# jar.net
KiCad netlist of a schematic drawn in EAGLE
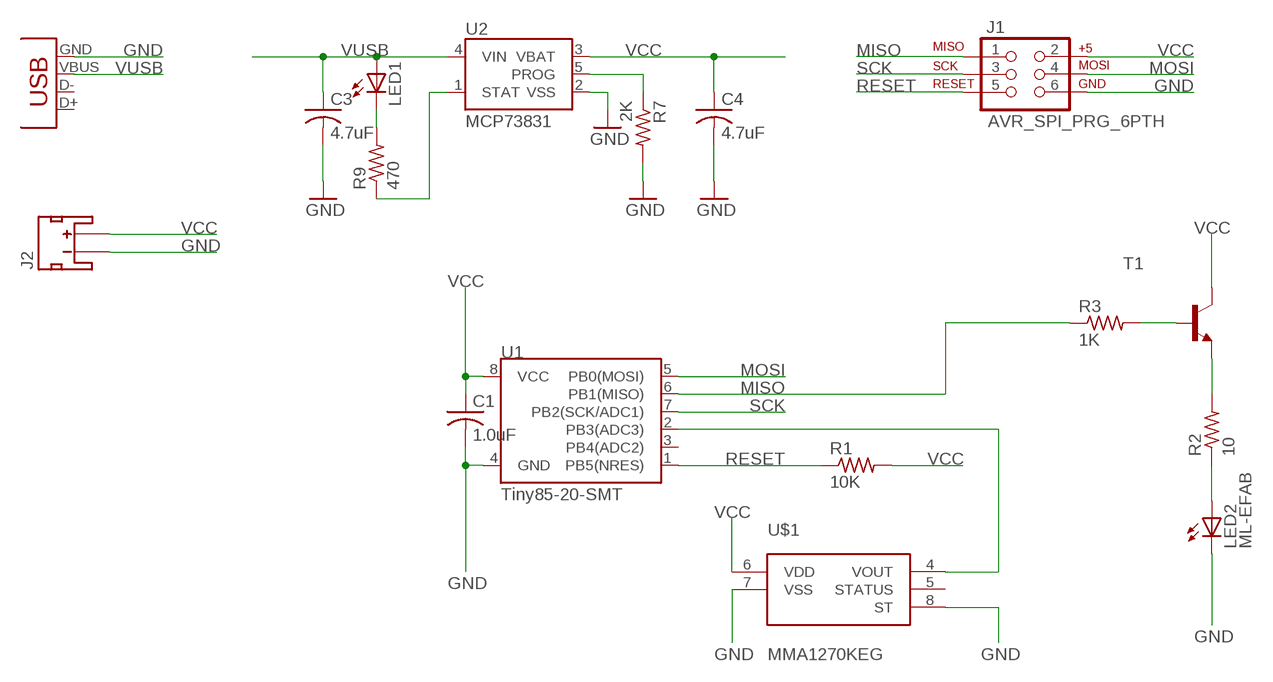
[diagram p0: schematic, sheet 1]

(export (version "E")
  (design (tool "Eeschema 10.0.6"))
  (components
    (comp (ref "C1")
      (value "1.0uF")
      (footprint "eagle-import:C1206")
      (libsource (lib "eagle-import") (part "C-USC1206"))
    )
    (comp (ref "C3")
      (value "4.7uF")
      (footprint "eagle-import:C1206")
      (libsource (lib "eagle-import") (part "C-USC1206"))
    )
    (comp (ref "C4")
      (value "4.7uF")
      (footprint "eagle-import:C1206")
      (libsource (lib "eagle-import") (part "C-USC1206"))
    )
    (comp (ref "J1")
      (value "AVR_SPI_PRG_6PTH")
      (footprint "eagle-import:2X3")
      (libsource (lib "eagle-import") (part "AVR_SPI_PRG_6PTH"))
    )
    (comp (ref "J2")
      (value "JST_2MM_MALE")
      (footprint "eagle-import:JST-2-SMD")
      (libsource (lib "eagle-import") (part "JST_2MM_MALE"))
    )
    (comp (ref "JP1")
      (value "USB-B-VERTICAL")
      (footprint "eagle-import:USB_MINIB_VERTICAL")
      (libsource (lib "eagle-import") (part "USB-B-VERTICAL"))
    )
    (comp (ref "LED1")
      (value "LEDSMT1206")
      (footprint "eagle-import:1206")
      (libsource (lib "eagle-import") (part "LEDSMT1206"))
    )
    (comp (ref "LED2")
      (value "ML-EFAB")
      (footprint "eagle-import:ML-E-FAB")
      (libsource (lib "eagle-import") (part "ML-EFAB"))
    )
    (comp (ref "R1")
      (value "10K")
      (footprint "eagle-import:R1206")
      (libsource (lib "eagle-import") (part "R-US_R1206"))
    )
    (comp (ref "R2")
      (value "10")
      (footprint "eagle-import:R1206")
      (libsource (lib "eagle-import") (part "R-US_R1206"))
    )
    (comp (ref "R3")
      (value "1K")
      (footprint "eagle-import:R1206")
      (libsource (lib "eagle-import") (part "R-US_R1206"))
    )
    (comp (ref "R7")
      (value "2K")
      (footprint "eagle-import:R1206")
      (libsource (lib "eagle-import") (part "R-US_R1206"))
    )
    (comp (ref "R9")
      (value "470")
      (footprint "eagle-import:R1206")
      (libsource (lib "eagle-import") (part "R-US_R1206"))
    )
    (comp (ref "T1")
      (value "MMBT3904LT1-NPN-SOT23-BEC")
      (footprint "eagle-import:SOT23-BEC")
      (libsource (lib "eagle-import") (part "-NPN-SOT23-BECMMBT3904LT1"))
    )
    (comp (ref "U$1")
      (value "MMA1270KEG")
      (footprint "eagle-import:SOIC16")
      (libsource (lib "eagle-import") (part "MMA1270KEG"))
    )
    (comp (ref "U1")
      (value "Tiny85-20-SMT")
      (footprint "eagle-import:SO08-EIAJ")
      (libsource (lib "eagle-import") (part "ATTINY45TINY85-20-SMT"))
    )
    (comp (ref "U2")
      (value "MCP73831")
      (footprint "eagle-import:SOT23-5")
      (libsource (lib "eagle-import") (part "MCP73831"))
    )
  )
  (nets
    (net (code "1") (name "/MISO") (class "Default")
      (node (ref "J1") (pin "1") (pinfunction "1_1") (pintype "passive"))
      (node (ref "R3") (pin "1") (pinfunction "1_1") (pintype "passive"))
      (node (ref "U1") (pin "6") (pinfunction "PB1(MISO)_6") (pintype "bidirectional"))
    )
    (net (code "2") (name "/MOSI") (class "Default")
      (node (ref "J1") (pin "4") (pinfunction "4_4") (pintype "passive"))
      (node (ref "U1") (pin "5") (pinfunction "PB0(MOSI)_5") (pintype "bidirectional"))
    )
    (net (code "3") (name "/RESET") (class "Default")
      (node (ref "J1") (pin "5") (pinfunction "5_5") (pintype "passive"))
      (node (ref "R1") (pin "1") (pinfunction "1_1") (pintype "passive"))
      (node (ref "U1") (pin "1") (pinfunction "PB5(NRES)_1") (pintype "bidirectional"))
    )
    (net (code "4") (name "/SCK") (class "Default")
      (node (ref "J1") (pin "3") (pinfunction "3_3") (pintype "passive"))
      (node (ref "U1") (pin "7") (pinfunction "PB2(SCK/ADC1)_7") (pintype "bidirectional"))
    )
    (net (code "5") (name "/VCC") (class "Default")
      (node (ref "C1") (pin "1") (pinfunction "1_1") (pintype "passive"))
      (node (ref "C4") (pin "1") (pinfunction "1_1") (pintype "passive"))
      (node (ref "J1") (pin "2") (pinfunction "2_2") (pintype "passive"))
      (node (ref "J2") (pin "2") (pinfunction "+_2") (pintype "bidirectional"))
      (node (ref "R1") (pin "2") (pinfunction "2_2") (pintype "passive"))
      (node (ref "T1") (pin "C") (pinfunction "C_C") (pintype "passive"))
      (node (ref "U$1") (pin "6") (pinfunction "VDD_6") (pintype "bidirectional"))
      (node (ref "U1") (pin "8") (pinfunction "VCC_8") (pintype "bidirectional"))
      (node (ref "U2") (pin "3") (pinfunction "VBAT_3") (pintype "power_in"))
    )
    (net (code "6") (name "/VUSB") (class "Default")
      (node (ref "C3") (pin "1") (pinfunction "1_1") (pintype "passive"))
      (node (ref "JP1") (pin "VBUS") (pinfunction "VBUS_VBUS") (pintype "bidirectional"))
      (node (ref "LED1") (pin "A") (pinfunction "A_A") (pintype "passive"))
      (node (ref "U2") (pin "4") (pinfunction "VIN_4") (pintype "power_in"))
    )
    (net (code "7") (name "GND") (class "Default")
      (node (ref "C1") (pin "2") (pinfunction "2_2") (pintype "passive"))
      (node (ref "C3") (pin "2") (pinfunction "2_2") (pintype "passive"))
      (node (ref "C4") (pin "2") (pinfunction "2_2") (pintype "passive"))
      (node (ref "J1") (pin "6") (pinfunction "6_6") (pintype "passive"))
      (node (ref "J2") (pin "1") (pinfunction "-_1") (pintype "bidirectional"))
      (node (ref "JP1") (pin "GND") (pinfunction "GND_GND") (pintype "bidirectional"))
      (node (ref "LED2") (pin "C@1") (pinfunction "C_C@1") (pintype "passive"))
      (node (ref "R7") (pin "2") (pinfunction "2_2") (pintype "passive"))
      (node (ref "U$1") (pin "7") (pinfunction "VSS_7") (pintype "bidirectional"))
      (node (ref "U$1") (pin "8") (pinfunction "ST_8") (pintype "bidirectional"))
      (node (ref "U1") (pin "4") (pinfunction "GND_4") (pintype "bidirectional"))
      (node (ref "U2") (pin "2") (pinfunction "VSS_2") (pintype "power_in"))
    )
    (net (code "8") (name "Net-(LED1-PadC)") (class "Default")
      (node (ref "LED1") (pin "C") (pinfunction "C_C") (pintype "passive"))
      (node (ref "R9") (pin "2") (pinfunction "2_2") (pintype "passive"))
    )
    (net (code "9") (name "Net-(LED2A-A-PadA@1)") (class "Default")
      (node (ref "LED2") (pin "A@1") (pinfunction "A_A@1") (pintype "passive"))
      (node (ref "R2") (pin "1") (pinfunction "1_1") (pintype "passive"))
    )
    (net (code "10") (name "Net-(R2-Pad2)") (class "Default")
      (node (ref "R2") (pin "2") (pinfunction "2_2") (pintype "passive"))
      (node (ref "T1") (pin "E") (pinfunction "E_E") (pintype "passive"))
    )
    (net (code "11") (name "Net-(R3-Pad2)") (class "Default")
      (node (ref "R3") (pin "2") (pinfunction "2_2") (pintype "passive"))
      (node (ref "T1") (pin "B") (pinfunction "B_B") (pintype "passive"))
    )
    (net (code "12") (name "Net-(U$1-VOUT)") (class "Default")
      (node (ref "U$1") (pin "4") (pinfunction "VOUT_4") (pintype "bidirectional"))
      (node (ref "U1") (pin "2") (pinfunction "PB3(ADC3)_2") (pintype "bidirectional"))
    )
    (net (code "13") (name "Net-(U2-PROG)") (class "Default")
      (node (ref "R7") (pin "1") (pinfunction "1_1") (pintype "passive"))
      (node (ref "U2") (pin "5") (pinfunction "PROG_5") (pintype "input"))
    )
    (net (code "14") (name "Net-(U2-STAT)") (class "Default")
      (node (ref "R9") (pin "1") (pinfunction "1_1") (pintype "passive"))
      (node (ref "U2") (pin "1") (pinfunction "STAT_1") (pintype "output"))
    )
    (net (code "15") (name "unconnected-(J2-PAD1-PadNC1)") (class "Default")
      (node (ref "J2") (pin "NC1") (pinfunction "PAD1_NC1") (pintype "bidirectional"))
    )
    (net (code "16") (name "unconnected-(J2-PAD2-PadNC2)") (class "Default")
      (node (ref "J2") (pin "NC2") (pinfunction "PAD2_NC2") (pintype "bidirectional"))
    )
    (net (code "17") (name "unconnected-(JP1-PadD+)") (class "Default")
      (node (ref "JP1") (pin "D+") (pinfunction "D+_D+") (pintype "bidirectional"))
    )
    (net (code "18") (name "unconnected-(JP1-PadD-)") (class "Default")
      (node (ref "JP1") (pin "D-") (pinfunction "D-_D-") (pintype "bidirectional"))
    )
    (net (code "19") (name "unconnected-(LED2A-A-PadA@2)") (class "Default")
      (node (ref "LED2") (pin "A@2") (pinfunction "A_A@2") (pintype "passive"))
    )
    (net (code "20") (name "unconnected-(LED2A-C-PadC@2)") (class "Default")
      (node (ref "LED2") (pin "C@2") (pinfunction "C_C@2") (pintype "passive"))
    )
    (net (code "21") (name "unconnected-(U$1-STATUS-Pad5)") (class "Default")
      (node (ref "U$1") (pin "5") (pinfunction "STATUS_5") (pintype "bidirectional"))
    )
    (net (code "22") (name "unconnected-(U1-PB4(ADC2)-Pad3)") (class "Default")
      (node (ref "U1") (pin "3") (pinfunction "PB4(ADC2)_3") (pintype "bidirectional"))
    )
  )
)
